# Urzeitcode-18F16Q41-2.net
KiCad netlist of a schematic drawn in EAGLE
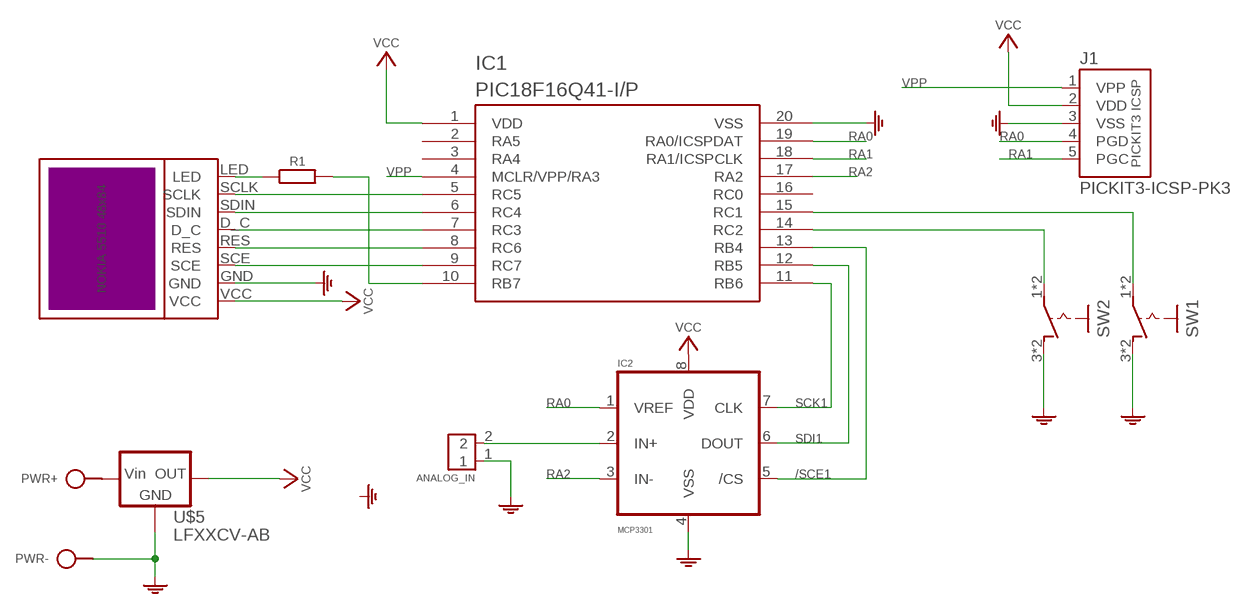
[diagram p0: schematic, sheet 1]

(export (version "E")
  (design (tool "Eeschema 10.0.6"))
  (components
    (comp (ref "ANALOG_IN")
      (value "CONN-2P2P/H")
      (footprint "eagle-import:CONN-2P")
      (libsource (lib "eagle-import") (part "CONN-2P2P/H"))
    )
    (comp (ref "IC1")
      (value "PIC18F16Q41-I/P")
      (footprint "eagle-import:DIL20-3_V")
      (libsource (lib "eagle-import") (part "PIC18F16Q41-I/P"))
    )
    (comp (ref "IC2")
      (value "MCP3301")
      (footprint "eagle-import:DIL08")
      (libsource (lib "eagle-import") (part "MCP3301"))
    )
    (comp (ref "J1")
      (value "PICKIT3-ICSP-PK3")
      (footprint "eagle-import:PIC-PK3")
      (libsource (lib "eagle-import") (part "PICKIT3-ICSP-PK3"))
    )
    (comp (ref "PWR")
      (value "SPAD+--+")
      (footprint "eagle-import:SPAD-+")
      (libsource (lib "eagle-import") (part "SPAD+--+"))
    )
    (comp (ref "R1")
      (value "R-H0204/15-V")
      (footprint "eagle-import:0204_15-V")
      (libsource (lib "eagle-import") (part "R-H0204/15-V"))
    )
    (comp (ref "SW1")
      (value "PB-1P-1T2P1T")
      (footprint "eagle-import:PB-2P1T")
      (libsource (lib "eagle-import") (part "PB-1P-1T2P1T"))
    )
    (comp (ref "SW2")
      (value "PB-1P-1T2P1T")
      (footprint "eagle-import:PB-2P1T")
      (libsource (lib "eagle-import") (part "PB-1P-1T2P1T"))
    )
    (comp (ref "U$2")
      (value "NOKIA-5510-48X84-MODULE")
      (footprint "eagle-import:MOD-LCD5110")
      (libsource (lib "eagle-import") (part "NOKIA-5510-48X84-MODULE"))
    )
    (comp (ref "U$5")
      (value "LFXXCV-AB")
      (footprint "eagle-import:TO220AB")
      (libsource (lib "eagle-import") (part "LFXXCV-AB"))
    )
  )
  (nets
    (net (code "1") (name "/RA0") (class "Default")
      (node (ref "IC1") (pin "19") (pinfunction "RA0/ICSPDAT_19") (pintype "passive"))
      (node (ref "IC2") (pin "1") (pinfunction "VREF_1") (pintype "input"))
      (node (ref "J1") (pin "4") (pinfunction "PGD_4") (pintype "passive"))
    )
    (net (code "2") (name "/RA1") (class "Default")
      (node (ref "IC1") (pin "18") (pinfunction "RA1/ICSPCLK_18") (pintype "passive"))
      (node (ref "J1") (pin "5") (pinfunction "PGC_5") (pintype "passive"))
    )
    (net (code "3") (name "/RA2") (class "Default")
      (node (ref "IC1") (pin "17") (pinfunction "RA2_17") (pintype "passive"))
      (node (ref "IC2") (pin "3") (pinfunction "IN-_3") (pintype "input"))
    )
    (net (code "4") (name "/SCK1") (class "Default")
      (node (ref "IC1") (pin "11") (pinfunction "RB6_11") (pintype "passive"))
      (node (ref "IC2") (pin "7") (pinfunction "CLK_7") (pintype "output"))
    )
    (net (code "5") (name "/SDI1") (class "Default")
      (node (ref "IC1") (pin "12") (pinfunction "RB5_12") (pintype "passive"))
      (node (ref "IC2") (pin "6") (pinfunction "DOUT_6") (pintype "passive"))
    )
    (net (code "6") (name "/VPP") (class "Default")
      (node (ref "IC1") (pin "4") (pinfunction "MCLR/VPP/RA3_4") (pintype "passive"))
      (node (ref "J1") (pin "1") (pinfunction "VPP_1") (pintype "passive"))
    )
    (net (code "7") (name "/{slash}SCE1") (class "Default")
      (node (ref "IC1") (pin "13") (pinfunction "RB4_13") (pintype "passive"))
      (node (ref "IC2") (pin "5") (pinfunction "/CS_5") (pintype "input"))
    )
    (net (code "8") (name "GND") (class "Default")
      (node (ref "ANALOG_IN") (pin "1") (pinfunction "1_1") (pintype "bidirectional"))
      (node (ref "IC1") (pin "20") (pinfunction "VSS_20") (pintype "passive"))
      (node (ref "IC2") (pin "4") (pinfunction "VSS_4") (pintype "power_in"))
      (node (ref "J1") (pin "3") (pinfunction "VSS_3") (pintype "passive"))
      (node (ref "PWR") (pin "1") (pinfunction "P$1_1") (pintype "passive"))
      (node (ref "SW1") (pin "3") (pinfunction "S_3") (pintype "passive"))
      (node (ref "SW1") (pin "4") (pinfunction "S_4") (pintype "passive"))
      (node (ref "SW2") (pin "3") (pinfunction "S_3") (pintype "passive"))
      (node (ref "SW2") (pin "4") (pinfunction "S_4") (pintype "passive"))
      (node (ref "U$2") (pin "GND") (pinfunction "GND_GND") (pintype "passive"))
      (node (ref "U$5") (pin "2") (pinfunction "GND_2") (pintype "input"))
    )
    (net (code "9") (name "Net-(IC1-RB7)") (class "Default")
      (node (ref "IC1") (pin "10") (pinfunction "RB7_10") (pintype "passive"))
      (node (ref "R1") (pin "2") (pinfunction "2_2") (pintype "passive"))
    )
    (net (code "10") (name "Net-(IC1-RC1)") (class "Default")
      (node (ref "IC1") (pin "15") (pinfunction "RC1_15") (pintype "passive"))
      (node (ref "SW1") (pin "1") (pinfunction "P_1") (pintype "passive"))
      (node (ref "SW1") (pin "2") (pinfunction "P_2") (pintype "passive"))
    )
    (net (code "11") (name "Net-(IC1-RC2)") (class "Default")
      (node (ref "IC1") (pin "14") (pinfunction "RC2_14") (pintype "passive"))
      (node (ref "SW2") (pin "1") (pinfunction "P_1") (pintype "passive"))
      (node (ref "SW2") (pin "2") (pinfunction "P_2") (pintype "passive"))
    )
    (net (code "12") (name "Net-(IC1-RC3)") (class "Default")
      (node (ref "IC1") (pin "7") (pinfunction "RC3_7") (pintype "passive"))
      (node (ref "U$2") (pin "D_C") (pinfunction "D_C_D_C") (pintype "passive"))
    )
    (net (code "13") (name "Net-(IC1-RC4)") (class "Default")
      (node (ref "IC1") (pin "6") (pinfunction "RC4_6") (pintype "passive"))
      (node (ref "U$2") (pin "SDIN") (pinfunction "SDIN_SDIN") (pintype "passive"))
    )
    (net (code "14") (name "Net-(IC1-RC5)") (class "Default")
      (node (ref "IC1") (pin "5") (pinfunction "RC5_5") (pintype "passive"))
      (node (ref "U$2") (pin "SCLK") (pinfunction "SCLK_SCLK") (pintype "passive"))
    )
    (net (code "15") (name "Net-(IC1-RC6)") (class "Default")
      (node (ref "IC1") (pin "8") (pinfunction "RC6_8") (pintype "passive"))
      (node (ref "U$2") (pin "RES") (pinfunction "RES_RES") (pintype "passive"))
    )
    (net (code "16") (name "Net-(IC1-RC7)") (class "Default")
      (node (ref "IC1") (pin "9") (pinfunction "RC7_9") (pintype "passive"))
      (node (ref "U$2") (pin "SCE") (pinfunction "SCE_SCE") (pintype "passive"))
    )
    (net (code "17") (name "Net-(IC2-IN+)") (class "Default")
      (node (ref "ANALOG_IN") (pin "2") (pinfunction "2_2") (pintype "bidirectional"))
      (node (ref "IC2") (pin "2") (pinfunction "IN+_2") (pintype "input"))
    )
    (net (code "18") (name "Net-(PWRA-P$1)") (class "Default")
      (node (ref "PWR") (pin "2") (pinfunction "P$1_2") (pintype "passive"))
      (node (ref "U$5") (pin "1") (pinfunction "VIN_1") (pintype "input"))
    )
    (net (code "19") (name "Net-(R1-Pad1)") (class "Default")
      (node (ref "R1") (pin "1") (pinfunction "1_1") (pintype "passive"))
      (node (ref "U$2") (pin "LED") (pinfunction "LED_LED") (pintype "passive"))
    )
    (net (code "20") (name "VCC") (class "Default")
      (node (ref "IC1") (pin "1") (pinfunction "VDD_1") (pintype "passive"))
      (node (ref "IC2") (pin "8") (pinfunction "VDD_8") (pintype "power_in"))
      (node (ref "J1") (pin "2") (pinfunction "VDD_2") (pintype "passive"))
      (node (ref "U$2") (pin "VCC") (pinfunction "VCC_VCC") (pintype "passive"))
      (node (ref "U$5") (pin "3") (pinfunction "VOUT_3") (pintype "output"))
    )
    (net (code "21") (name "unconnected-(IC1-RA4-Pad3)") (class "Default")
      (node (ref "IC1") (pin "3") (pinfunction "RA4_3") (pintype "passive"))
    )
    (net (code "22") (name "unconnected-(IC1-RA5-Pad2)") (class "Default")
      (node (ref "IC1") (pin "2") (pinfunction "RA5_2") (pintype "passive"))
    )
    (net (code "23") (name "unconnected-(IC1-RC0-Pad16)") (class "Default")
      (node (ref "IC1") (pin "16") (pinfunction "RC0_16") (pintype "passive"))
    )
  )
)
